# Memory.net
KiCad netlist of a schematic drawn in Altium Designer
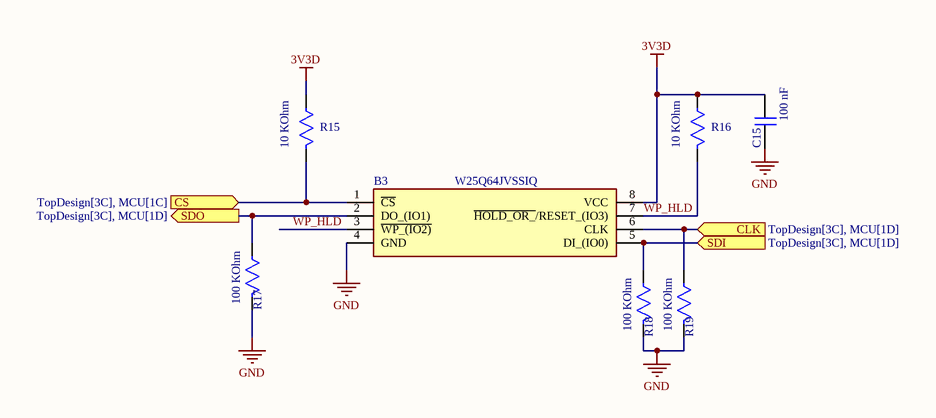
[diagram p0: Memory.SchDoc]

(export (version "E")
  (design (tool "Eeschema 10.0.6"))
  (components
    (comp (ref "B3")
      (value "W25Q64JVSSIQ")
      (footprint "W25Q64JVSSIQ")
      (description "64Mb Serial NOR Flash 133MHz SOP864Mbit 2.7V~3.6V 133MHz SPI SOIC-8-208mil Memory (ICs) ROHS")
      (libsource (lib "Aptinex_devices") (part "W25Q64JVSSIQ"))
    )
    (comp (ref "C15")
      (value "100 nF")
      (footprint "CAP_0603")
      (description "Cap SMD.")
      (libsource (lib "Aptinex_discrete") (part "Cap SMD"))
    )
    (comp (ref "R15")
      (value "10 KOhm")
      (footprint "Res_0603")
      (description "SMD Resistor")
      (fields (field (name "MP") "RC0805FR-07330RL") (field (name "MF") "Yageo"))
      (libsource (lib "Aptinex_discrete") (part "Res smd"))
    )
    (comp (ref "R16")
      (value "10 KOhm")
      (footprint "Res_0603")
      (description "SMD Resistor")
      (fields (field (name "MP") "RC0805FR-07330RL") (field (name "MF") "Yageo"))
      (libsource (lib "Aptinex_discrete") (part "Res smd"))
    )
    (comp (ref "R17")
      (value "100 KOhm")
      (footprint "Res_0603")
      (description "SMD Resistor")
      (fields (field (name "MP") "RC0805FR-07330RL") (field (name "MF") "Yageo"))
      (libsource (lib "Aptinex_discrete") (part "Res smd"))
    )
    (comp (ref "R18")
      (value "100 KOhm")
      (footprint "Res_0603")
      (description "SMD Resistor")
      (fields (field (name "MP") "RC0805FR-07330RL") (field (name "MF") "Yageo"))
      (libsource (lib "Aptinex_discrete") (part "Res smd"))
    )
    (comp (ref "R19")
      (value "100 KOhm")
      (footprint "Res_0603")
      (description "SMD Resistor")
      (fields (field (name "MP") "RC0805FR-07330RL") (field (name "MF") "Yageo"))
      (libsource (lib "Aptinex_discrete") (part "Res smd"))
    )
  )
  (nets
    (net (code "1") (name "/CLK") (class "Default")
      (node (ref "B3") (pin "6") (pinfunction "CLK_6") (pintype "passive"))
      (node (ref "R19") (pin "2") (pinfunction "2_2") (pintype "passive"))
    )
    (net (code "2") (name "/CS") (class "Default")
      (node (ref "B3") (pin "1") (pinfunction "~{CS}_1") (pintype "passive"))
      (node (ref "R15") (pin "1") (pinfunction "1_1") (pintype "passive"))
    )
    (net (code "3") (name "/SDI") (class "Default")
      (node (ref "B3") (pin "5") (pinfunction "DI_(IO0)_5") (pintype "passive"))
      (node (ref "R18") (pin "2") (pinfunction "2_2") (pintype "passive"))
    )
    (net (code "4") (name "/SDO") (class "Default")
      (node (ref "B3") (pin "2") (pinfunction "DO_(IO1)_2") (pintype "passive"))
      (node (ref "R17") (pin "2") (pinfunction "2_2") (pintype "passive"))
    )
    (net (code "5") (name "/WP_HLD") (class "Default")
      (node (ref "B3") (pin "3") (pinfunction "~{WP_(IO2)}_3") (pintype "passive"))
      (node (ref "B3") (pin "7") (pinfunction "~{HOLD_OR_}/RESET_(IO3)_7") (pintype "passive"))
      (node (ref "R16") (pin "1") (pinfunction "1_1") (pintype "passive"))
    )
    (net (code "6") (name "3V3D") (class "Default")
      (node (ref "B3") (pin "8") (pinfunction "VCC_8") (pintype "passive"))
      (node (ref "C15") (pin "2") (pinfunction "2_2") (pintype "passive"))
      (node (ref "R15") (pin "2") (pinfunction "2_2") (pintype "passive"))
      (node (ref "R16") (pin "2") (pinfunction "2_2") (pintype "passive"))
    )
    (net (code "7") (name "GND") (class "Default")
      (node (ref "B3") (pin "4") (pinfunction "GND_4") (pintype "passive"))
      (node (ref "C15") (pin "1") (pinfunction "1_1") (pintype "passive"))
      (node (ref "R17") (pin "1") (pinfunction "1_1") (pintype "passive"))
      (node (ref "R18") (pin "1") (pinfunction "1_1") (pintype "passive"))
      (node (ref "R19") (pin "1") (pinfunction "1_1") (pintype "passive"))
    )
  )
)
